# 01_MAIN.net
KiCad netlist of a schematic drawn in Altium Designer
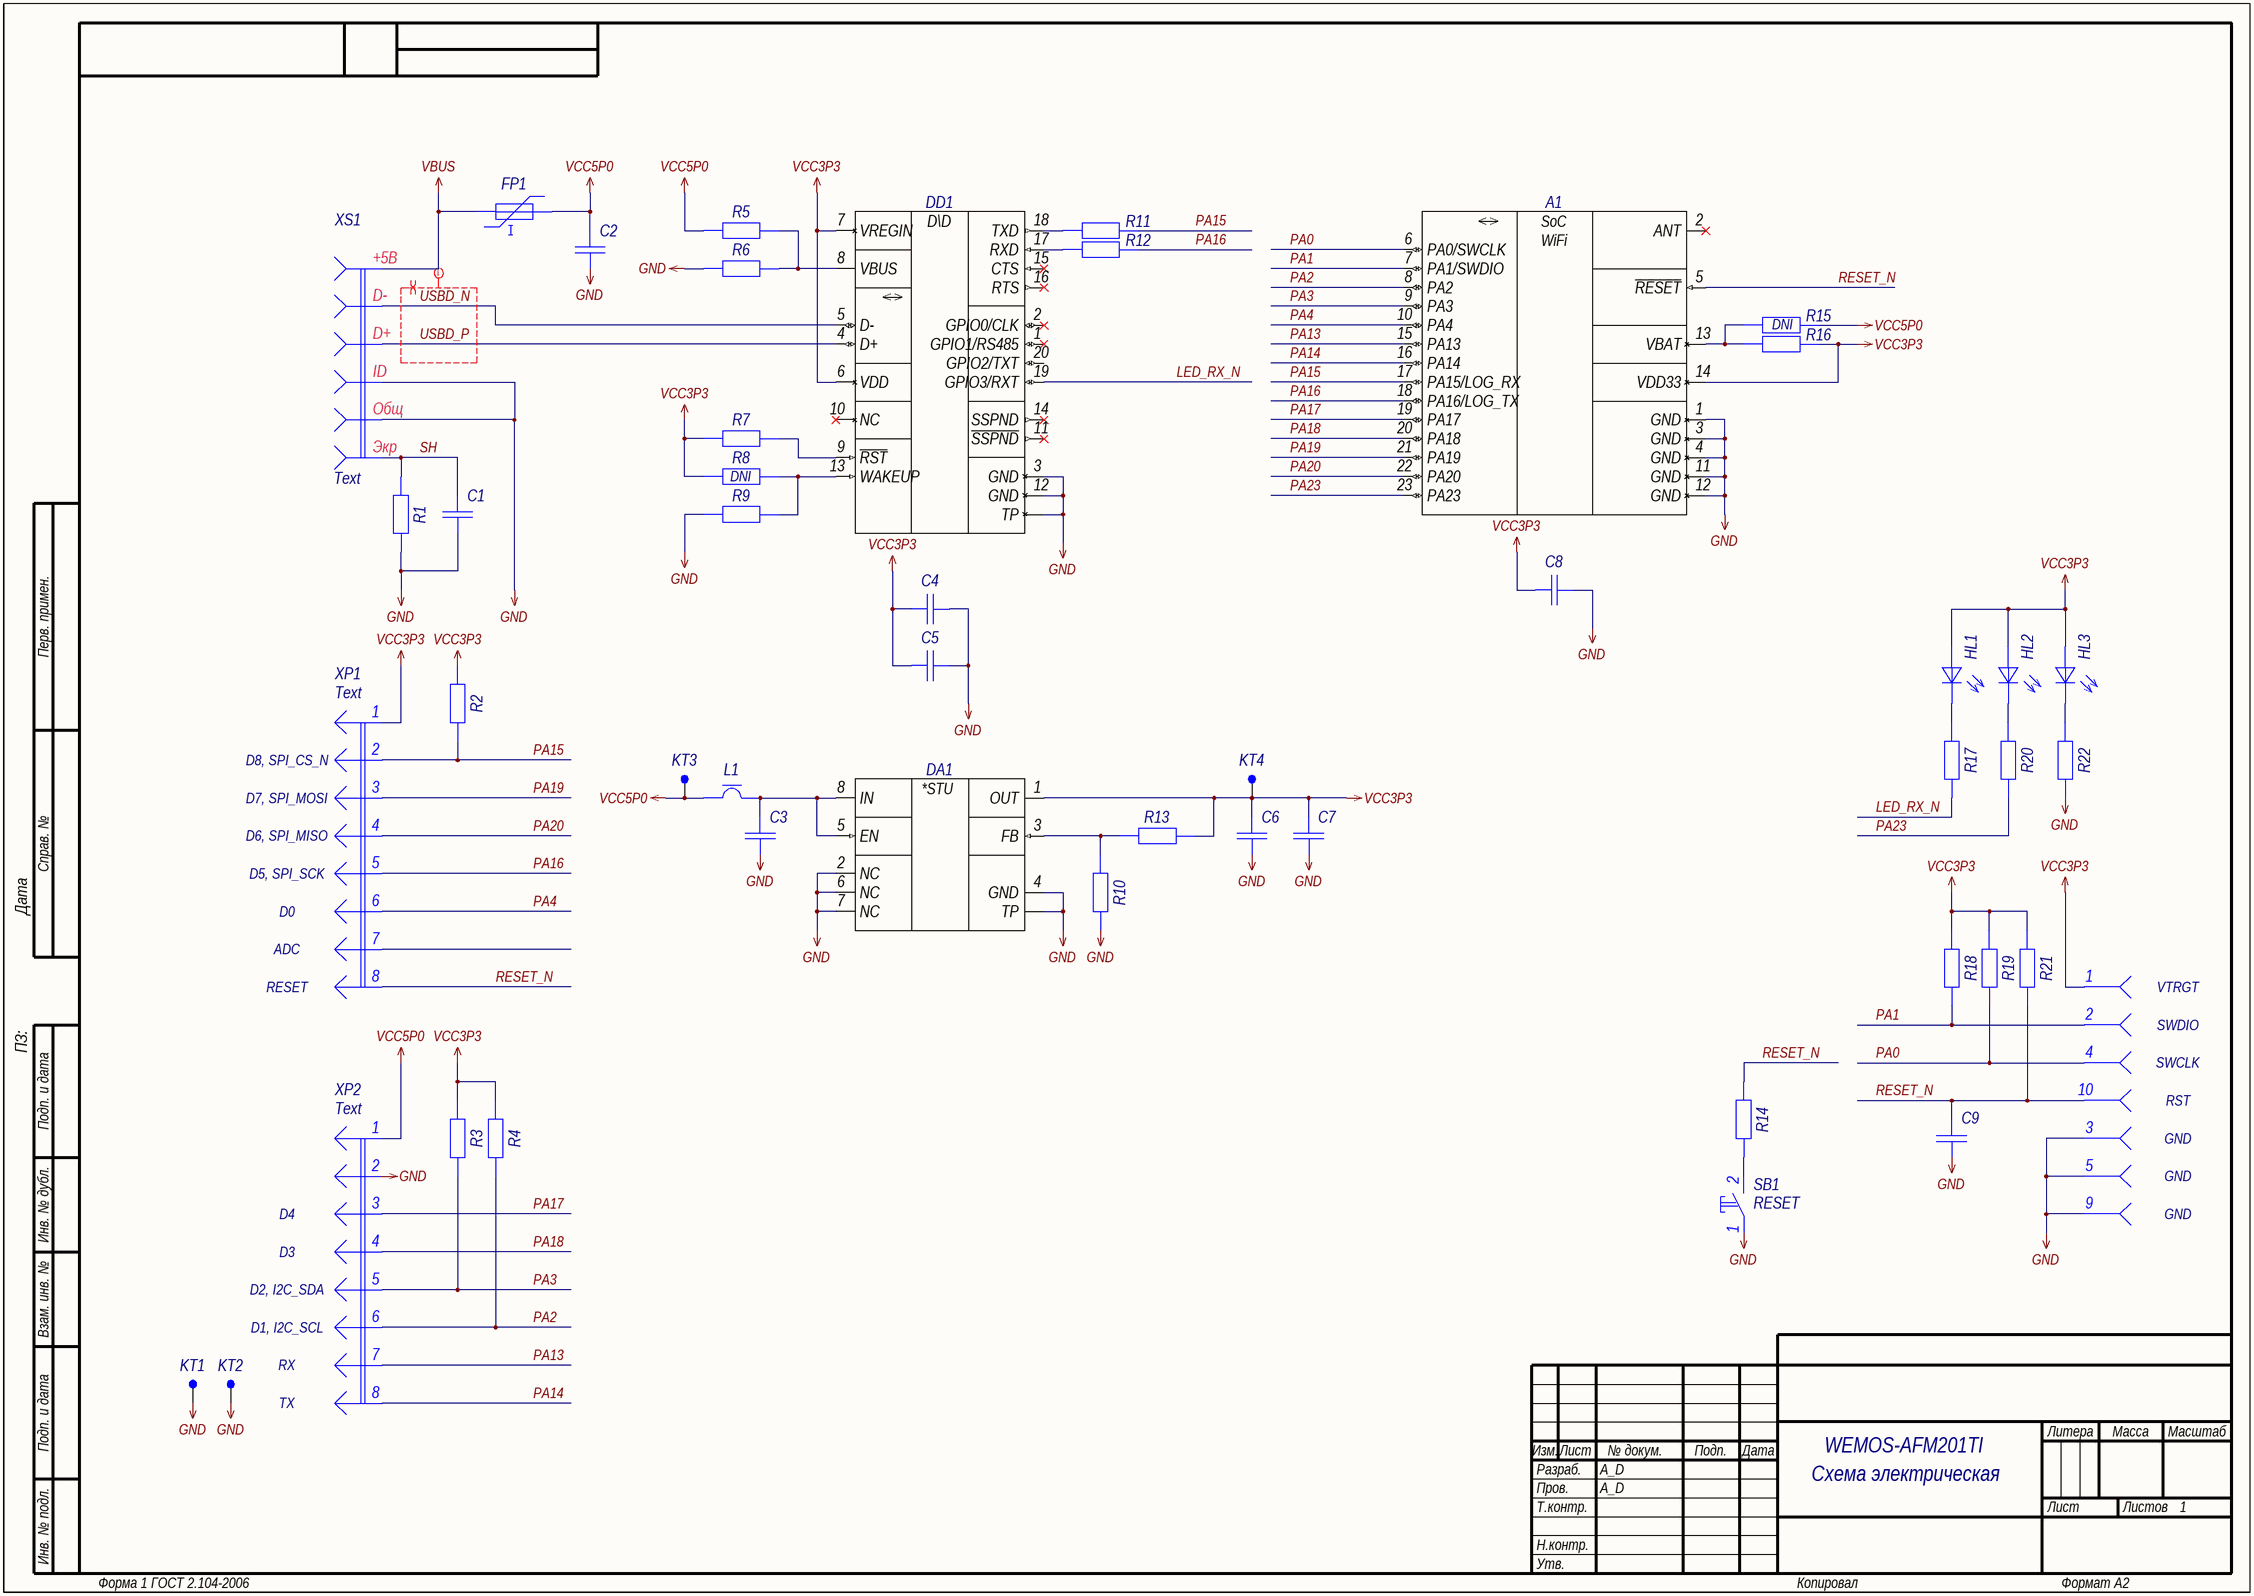
[diagram p0: 01_MAIN.SchDoc]

(export (version "E")
  (design (tool "Eeschema 10.0.6"))
  (components
    (comp (ref "A1")
      (value "AFM201Tx-Series")
      (footprint "AFM201Tx-Series")
      (fields
        (field (name "PART NUMBER") "AFM201TI")
        (field (name "MANUFACTURER") "99IOT")
        (field (name "PUBLISHER") "Andrew Danich")
      )
      (libsource (lib "ADLib") (part "AFM201Tx-Series"))
    )
    (comp (ref "C1")
      (value "Capacitor")
      (footprint "C0603_L")
      (fields
        (field (name "PART NUMBER") "GRM188R72A104KA35D")
        (field (name "VOLTAGE") "100V")
        (field (name "TOLERANCE") "±10%")
        (field (name "PUBLISHER") "Andrew Danich")
      )
      (libsource (lib "ADLib") (part "Capacitor"))
    )
    (comp (ref "C2")
      (value "Capacitor")
      (footprint "C0603_L")
      (fields
        (field (name "PART NUMBER") "GRM188R60J106ME47D")
        (field (name "VOLTAGE") "6.3V")
        (field (name "TOLERANCE") "±20%")
        (field (name "PUBLISHER") "Andrew Danich")
      )
      (libsource (lib "ADLib") (part "Capacitor"))
    )
    (comp (ref "C3")
      (value "Capacitor")
      (footprint "C0402_L")
      (fields
        (field (name "PART NUMBER") "GRM155R60J475ME87D")
        (field (name "VOLTAGE") "6.3V")
        (field (name "TOLERANCE") "±20%")
        (field (name "PUBLISHER") "Andrew Danich")
      )
      (libsource (lib "ADLib") (part "Capacitor"))
    )
    (comp (ref "C4")
      (value "Capacitor")
      (footprint "C0402_L")
      (fields
        (field (name "PART NUMBER") "GRM155R60J475ME87D")
        (field (name "VOLTAGE") "6.3V")
        (field (name "TOLERANCE") "±20%")
        (field (name "PUBLISHER") "Andrew Danich")
      )
      (libsource (lib "ADLib") (part "Capacitor"))
    )
    (comp (ref "C5")
      (value "Capacitor")
      (footprint "C0402_L")
      (fields
        (field (name "PART NUMBER") "GCM155R71C104KA55D")
        (field (name "VOLTAGE") "16V")
        (field (name "TOLERANCE") "±10%")
        (field (name "PUBLISHER") "Andrew Danich")
      )
      (libsource (lib "ADLib") (part "Capacitor"))
    )
    (comp (ref "C6")
      (value "Capacitor")
      (footprint "C0402_L")
      (fields
        (field (name "PART NUMBER") "GRM155R60J475ME87D")
        (field (name "VOLTAGE") "6.3V")
        (field (name "TOLERANCE") "±20%")
        (field (name "PUBLISHER") "Andrew Danich")
      )
      (libsource (lib "ADLib") (part "Capacitor"))
    )
    (comp (ref "C7")
      (value "Capacitor")
      (footprint "C0402_L")
      (fields
        (field (name "PART NUMBER") "GRM155R60J475ME87D")
        (field (name "VOLTAGE") "6.3V")
        (field (name "TOLERANCE") "±20%")
        (field (name "PUBLISHER") "Andrew Danich")
      )
      (libsource (lib "ADLib") (part "Capacitor"))
    )
    (comp (ref "C8")
      (value "Capacitor")
      (footprint "C0402_L")
      (fields
        (field (name "PART NUMBER") "GRM155R60J475ME87D")
        (field (name "VOLTAGE") "6.3V")
        (field (name "TOLERANCE") "±20%")
        (field (name "PUBLISHER") "Andrew Danich")
      )
      (libsource (lib "ADLib") (part "Capacitor"))
    )
    (comp (ref "C9")
      (value "Capacitor")
      (footprint "C0402_L")
      (fields
        (field (name "PART NUMBER") "GCM155R71C104KA55D")
        (field (name "VOLTAGE") "16V")
        (field (name "TOLERANCE") "±10%")
        (field (name "PUBLISHER") "Andrew Danich")
      )
      (libsource (lib "ADLib") (part "Capacitor"))
    )
    (comp (ref "DA1")
      (value "TPS73701DRB")
      (footprint "VSON-8_065P300X300X100_N")
      (fields
        (field (name "PART NUMBER") "TPS73701DRBR")
        (field (name "MANUFACTURER") "Texas Instruments")
        (field (name "PUBLISHER") "Andrew Danich")
      )
      (libsource (lib "ADLib") (part "TPS73701DRB"))
    )
    (comp (ref "DD1")
      (value "CP2102N-xxx-GQFN20")
      (footprint "QFN-20_050P300X300X080_N")
      (fields
        (field (name "PART NUMBER") "CP2102N-A01-GQFN20")
        (field (name "MANUFACTURER") "Silicon Labs")
        (field (name "PUBLISHER") "Andrew Danich")
      )
      (libsource (lib "ADLib") (part "CP2102N-xxx-GQFN20"))
    )
    (comp (ref "FP1")
      (value "Fuse_PTC")
      (footprint "F0603_L_H075")
      (fields (field (name "PART NUMBER") "0603L100SLYR") (field (name "MANUFACTURER") "Littelfuse"))
      (libsource (lib "ADLib") (part "Fuse_PTC"))
    )
    (comp (ref "HL1")
      (value "RX")
      (footprint "LD0402_L")
      (fields
        (field (name "PART NUMBER") "KPHHS-1005SURCK")
        (field (name "MANUFACTURER") "Kingbright")
        (field (name "PUBLISHER") "Andrew Danich")
      )
      (libsource (lib "ADLib") (part "Led-1"))
    )
    (comp (ref "HL2")
      (value "USER")
      (footprint "LD0402_L")
      (fields
        (field (name "PART NUMBER") "KPHHS-1005QBC-D-V")
        (field (name "MANUFACTURER") "Kingbright")
        (field (name "PUBLISHER") "Andrew Danich")
      )
      (libsource (lib "ADLib") (part "Led-1"))
    )
    (comp (ref "HL3")
      (value "POWER")
      (footprint "LD0402_L")
      (fields
        (field (name "PART NUMBER") "KPHHS-1005CGCK")
        (field (name "MANUFACTURER") "Kingbright")
        (field (name "PUBLISHER") "Andrew Danich")
      )
      (libsource (lib "ADLib") (part "Led-1"))
    )
    (comp (ref "KT1")
      (value "GND")
      (footprint "TP-SMT-R-0.8mm")
      (fields (field (name "PART NUMBER") "TestPoint-SMT-GND") (field (name "PUBLISHER") "Andrew Danich"))
      (libsource (lib "ADLib") (part "TP-S-1"))
    )
    (comp (ref "KT2")
      (value "GND")
      (footprint "TP-SMT-R-0.8mm")
      (fields (field (name "PART NUMBER") "TestPoint-SMT-GND") (field (name "PUBLISHER") "Andrew Danich"))
      (libsource (lib "ADLib") (part "TP-S-1"))
    )
    (comp (ref "KT3")
      (value "5P0")
      (footprint "TP-SMT-C-0.5mm")
      (fields (field (name "PART NUMBER") "TestPoint-SMT") (field (name "PUBLISHER") "Andrew Danich"))
      (libsource (lib "ADLib") (part "TP-S-1"))
    )
    (comp (ref "KT4")
      (value "3P3")
      (footprint "TP-SMT-C-0.5mm")
      (fields (field (name "PART NUMBER") "TestPoint-SMT") (field (name "PUBLISHER") "Andrew Danich"))
      (libsource (lib "ADLib") (part "TP-S-1"))
    )
    (comp (ref "L1")
      (value "FerriteBead")
      (footprint "L0402_L")
      (fields
        (field (name "PART NUMBER") "BLM15PD121SN1D")
        (field (name "TOLERANCE") "±25%")
        (field (name "MANUFACTURER") "Murata")
        (field (name "PUBLISHER") "Andrew Danich")
      )
      (libsource (lib "ADLib") (part "FerriteBead"))
    )
    (comp (ref "R1")
      (value "Resistor")
      (footprint "R0603_L")
      (fields
        (field (name "PART NUMBER") "RC0603JR-070R")
        (field (name "TOLERANCE") "±5%")
        (field (name "MANUFACTURER") "Yageo")
        (field (name "PUBLISHER") "Andrew Danich")
      )
      (libsource (lib "ADLib") (part "Resistor"))
    )
    (comp (ref "R2")
      (value "Resistor")
      (footprint "R0402_L")
      (fields
        (field (name "PART NUMBER") "RC0402JR-0710KL")
        (field (name "TOLERANCE") "±5%")
        (field (name "MANUFACTURER") "Yageo")
        (field (name "PUBLISHER") "Andrew Danich")
      )
      (libsource (lib "ADLib") (part "Resistor"))
    )
    (comp (ref "R3")
      (value "Resistor")
      (footprint "R0402_L")
      (fields
        (field (name "PART NUMBER") "RC0402JR-0710KL")
        (field (name "TOLERANCE") "±5%")
        (field (name "MANUFACTURER") "Yageo")
        (field (name "PUBLISHER") "Andrew Danich")
      )
      (libsource (lib "ADLib") (part "Resistor"))
    )
    (comp (ref "R4")
      (value "Resistor")
      (footprint "R0402_L")
      (fields
        (field (name "PART NUMBER") "RC0402JR-0710KL")
        (field (name "TOLERANCE") "±5%")
        (field (name "MANUFACTURER") "Yageo")
        (field (name "PUBLISHER") "Andrew Danich")
      )
      (libsource (lib "ADLib") (part "Resistor"))
    )
    (comp (ref "R5")
      (value "Resistor")
      (footprint "R0402_L")
      (fields
        (field (name "PART NUMBER") "RC0402FR-0722K1L")
        (field (name "TOLERANCE") "±1%")
        (field (name "MANUFACTURER") "Yageo")
        (field (name "PUBLISHER") "Andrew Danich")
      )
      (libsource (lib "ADLib") (part "Resistor"))
    )
    (comp (ref "R6")
      (value "Resistor")
      (footprint "R0402_L")
      (fields
        (field (name "PART NUMBER") "RC0402FR-0747KL")
        (field (name "TOLERANCE") "±1%")
        (field (name "MANUFACTURER") "Yageo")
        (field (name "PUBLISHER") "Andrew Danich")
      )
      (libsource (lib "ADLib") (part "Resistor"))
    )
    (comp (ref "R7")
      (value "Resistor")
      (footprint "R0402_L")
      (fields
        (field (name "PART NUMBER") "RC0402JR-0710KL")
        (field (name "TOLERANCE") "±5%")
        (field (name "MANUFACTURER") "Yageo")
        (field (name "PUBLISHER") "Andrew Danich")
      )
      (libsource (lib "ADLib") (part "Resistor"))
    )
    (comp (ref "R8")
      (value "Resistor")
      (footprint "R0402_L")
      (fields
        (field (name "PART NUMBER") "RC0402JR-0710KL")
        (field (name "TOLERANCE") "±5%")
        (field (name "MANUFACTURER") "Yageo")
        (field (name "PUBLISHER") "Andrew Danich")
      )
      (libsource (lib "ADLib") (part "Resistor"))
    )
    (comp (ref "R9")
      (value "Resistor")
      (footprint "R0402_L")
      (fields
        (field (name "PART NUMBER") "RC0402JR-070RL")
        (field (name "TOLERANCE") "±5%")
        (field (name "MANUFACTURER") "Yageo")
        (field (name "PUBLISHER") "Andrew Danich")
      )
      (libsource (lib "ADLib") (part "Resistor"))
    )
    (comp (ref "R10")
      (value "Resistor")
      (footprint "R0402_L")
      (fields
        (field (name "PART NUMBER") "RC0402FR-0712KL")
        (field (name "TOLERANCE") "±1%")
        (field (name "MANUFACTURER") "Yageo")
        (field (name "PUBLISHER") "Andrew Danich")
      )
      (libsource (lib "ADLib") (part "Resistor"))
    )
    (comp (ref "R11")
      (value "Resistor")
      (footprint "R0402_L")
      (fields
        (field (name "PART NUMBER") "RC0402JR-070RL")
        (field (name "TOLERANCE") "±5%")
        (field (name "MANUFACTURER") "Yageo")
        (field (name "PUBLISHER") "Andrew Danich")
      )
      (libsource (lib "ADLib") (part "Resistor"))
    )
    (comp (ref "R12")
      (value "Resistor")
      (footprint "R0402_L")
      (fields
        (field (name "PART NUMBER") "RC0402JR-070RL")
        (field (name "TOLERANCE") "±5%")
        (field (name "MANUFACTURER") "Yageo")
        (field (name "PUBLISHER") "Andrew Danich")
      )
      (libsource (lib "ADLib") (part "Resistor"))
    )
    (comp (ref "R13")
      (value "Resistor")
      (footprint "R0402_L")
      (fields
        (field (name "PART NUMBER") "RC0402FR-0722K1L")
        (field (name "TOLERANCE") "±1%")
        (field (name "MANUFACTURER") "Yageo")
        (field (name "PUBLISHER") "Andrew Danich")
      )
      (libsource (lib "ADLib") (part "Resistor"))
    )
    (comp (ref "R14")
      (value "Resistor")
      (footprint "R0402_L")
      (fields
        (field (name "PART NUMBER") "RC0402JR-0720RL")
        (field (name "TOLERANCE") "±5%")
        (field (name "MANUFACTURER") "Yageo")
        (field (name "PUBLISHER") "Andrew Danich")
      )
      (libsource (lib "ADLib") (part "Resistor"))
    )
    (comp (ref "R15")
      (value "Resistor")
      (footprint "R0402_L")
      (fields
        (field (name "PART NUMBER") "RC0402JR-070RL")
        (field (name "TOLERANCE") "±5%")
        (field (name "MANUFACTURER") "Yageo")
        (field (name "PUBLISHER") "Andrew Danich")
      )
      (libsource (lib "ADLib") (part "Resistor"))
    )
    (comp (ref "R16")
      (value "Resistor")
      (footprint "R0402_L")
      (fields
        (field (name "PART NUMBER") "RC0402JR-070RL")
        (field (name "TOLERANCE") "±5%")
        (field (name "MANUFACTURER") "Yageo")
        (field (name "PUBLISHER") "Andrew Danich")
      )
      (libsource (lib "ADLib") (part "Resistor"))
    )
    (comp (ref "R17")
      (value "Resistor")
      (footprint "R0402_L")
      (fields
        (field (name "PART NUMBER") "RC0402JR-071KL")
        (field (name "TOLERANCE") "±5%")
        (field (name "MANUFACTURER") "Yageo")
        (field (name "PUBLISHER") "Andrew Danich")
      )
      (libsource (lib "ADLib") (part "Resistor"))
    )
    (comp (ref "R18")
      (value "Resistor")
      (footprint "R0402_L")
      (fields
        (field (name "PART NUMBER") "RC0402JR-0710KL")
        (field (name "TOLERANCE") "±5%")
        (field (name "MANUFACTURER") "Yageo")
        (field (name "PUBLISHER") "Andrew Danich")
      )
      (libsource (lib "ADLib") (part "Resistor"))
    )
    (comp (ref "R19")
      (value "Resistor")
      (footprint "R0402_L")
      (fields
        (field (name "PART NUMBER") "RC0402JR-0710KL")
        (field (name "TOLERANCE") "±5%")
        (field (name "MANUFACTURER") "Yageo")
        (field (name "PUBLISHER") "Andrew Danich")
      )
      (libsource (lib "ADLib") (part "Resistor"))
    )
    (comp (ref "R20")
      (value "Resistor")
      (footprint "R0402_L")
      (fields
        (field (name "PART NUMBER") "RC0402JR-071KL")
        (field (name "TOLERANCE") "±5%")
        (field (name "MANUFACTURER") "Yageo")
        (field (name "PUBLISHER") "Andrew Danich")
      )
      (libsource (lib "ADLib") (part "Resistor"))
    )
    (comp (ref "R21")
      (value "Resistor")
      (footprint "R0402_L")
      (fields
        (field (name "PART NUMBER") "RC0402JR-0710KL")
        (field (name "TOLERANCE") "±5%")
        (field (name "MANUFACTURER") "Yageo")
        (field (name "PUBLISHER") "Andrew Danich")
      )
      (libsource (lib "ADLib") (part "Resistor"))
    )
    (comp (ref "R22")
      (value "Resistor")
      (footprint "R0402_L")
      (fields
        (field (name "PART NUMBER") "RC0402JR-071KL")
        (field (name "TOLERANCE") "±5%")
        (field (name "MANUFACTURER") "Yageo")
        (field (name "PUBLISHER") "Andrew Danich")
      )
      (libsource (lib "ADLib") (part "Resistor"))
    )
    (comp (ref "SB1")
      (value "RESET")
      (footprint "1TS003B-Series")
      (fields
        (field (name "PART NUMBER") "1TS003B-1600-3500A-CT")
        (field (name "MANUFACTURER") "Hongyuan Precision")
        (field (name "PUBLISHER") "Andrew Danich")
      )
      (libsource (lib "ADLib") (part "BT-01x-01p"))
    )
    (comp (ref "XP1")
      (value "Text")
      (footprint "PLS-8")
      (fields (field (name "PART NUMBER") "PLS-8") (field (name "PUBLISHER") "Andrew Danich"))
      (libsource (lib "ADLib") (part "Con-8-M"))
    )
    (comp (ref "XP2")
      (value "Text")
      (footprint "PLS-8")
      (fields (field (name "PART NUMBER") "PLS-8") (field (name "PUBLISHER") "Andrew Danich"))
      (libsource (lib "ADLib") (part "Con-8-M"))
    )
    (comp (ref "XS1")
      (value "Text")
      (footprint "1981568-1")
      (fields
        (field (name "PART NUMBER") "1981568-1")
        (field (name "MANUFACTURER") "TE Connectivity")
        (field (name "PUBLISHER") "Andrew Danich")
      )
      (libsource (lib "ADLib") (part "Con-6-F-USB"))
    )
    (comp (ref "XS2")
      (value "JTAG")
      (footprint "XF2M-1015-1A")
      (fields
        (field (name "PART NUMBER") "XF2M-1015-1A")
        (field (name "MANUFACTURER") "Omron Electronics")
        (field (name "PUBLISHER") "Viktor Klishin")
      )
      (libsource (lib "ADLib") (part "Con-10-F_S"))
    )
  )
  (nets
    (net (code "1") (name "/LED_RX_N") (class "Default")
      (node (ref "DD1") (pin "19") (pinfunction "GPIO3/RXT_19") (pintype "bidirectional"))
      (node (ref "R17") (pin "1") (pinfunction "1_1") (pintype "passive"))
    )
    (net (code "2") (name "/PA0") (class "Default")
      (node (ref "A1") (pin "6") (pinfunction "PA0/SWCLK_6") (pintype "bidirectional"))
      (node (ref "R19") (pin "2") (pinfunction "2_2") (pintype "passive"))
      (node (ref "XS2") (pin "4") (pintype "passive"))
    )
    (net (code "3") (name "/PA1") (class "Default")
      (node (ref "A1") (pin "7") (pinfunction "PA1/SWDIO_7") (pintype "bidirectional"))
      (node (ref "R18") (pin "2") (pinfunction "2_2") (pintype "passive"))
      (node (ref "XS2") (pin "2") (pintype "passive"))
    )
    (net (code "4") (name "/PA2") (class "Default")
      (node (ref "A1") (pin "8") (pinfunction "PA2_8") (pintype "bidirectional"))
      (node (ref "R4") (pin "2") (pinfunction "2_2") (pintype "passive"))
      (node (ref "XP2") (pin "6") (pintype "passive"))
    )
    (net (code "5") (name "/PA3") (class "Default")
      (node (ref "A1") (pin "9") (pinfunction "PA3_9") (pintype "bidirectional"))
      (node (ref "R3") (pin "2") (pinfunction "2_2") (pintype "passive"))
      (node (ref "XP2") (pin "5") (pintype "passive"))
    )
    (net (code "6") (name "/PA4") (class "Default")
      (node (ref "A1") (pin "10") (pinfunction "PA4_10") (pintype "bidirectional"))
      (node (ref "XP1") (pin "6") (pintype "passive"))
    )
    (net (code "7") (name "/PA13") (class "Default")
      (node (ref "A1") (pin "15") (pinfunction "PA13_15") (pintype "bidirectional"))
      (node (ref "XP2") (pin "7") (pintype "passive"))
    )
    (net (code "8") (name "/PA14") (class "Default")
      (node (ref "A1") (pin "16") (pinfunction "PA14_16") (pintype "bidirectional"))
      (node (ref "XP2") (pin "8") (pintype "passive"))
    )
    (net (code "9") (name "/PA15") (class "Default")
      (node (ref "A1") (pin "17") (pinfunction "PA15/LOG_RX_17") (pintype "bidirectional"))
      (node (ref "R11") (pin "2") (pinfunction "2_2") (pintype "passive"))
      (node (ref "R2") (pin "2") (pinfunction "2_2") (pintype "passive"))
      (node (ref "XP1") (pin "2") (pintype "passive"))
    )
    (net (code "10") (name "/PA16") (class "Default")
      (node (ref "A1") (pin "18") (pinfunction "PA16/LOG_TX_18") (pintype "bidirectional"))
      (node (ref "R12") (pin "2") (pinfunction "2_2") (pintype "passive"))
      (node (ref "XP1") (pin "5") (pintype "passive"))
    )
    (net (code "11") (name "/PA17") (class "Default")
      (node (ref "A1") (pin "19") (pinfunction "PA17_19") (pintype "bidirectional"))
      (node (ref "XP2") (pin "3") (pintype "passive"))
    )
    (net (code "12") (name "/PA18") (class "Default")
      (node (ref "A1") (pin "20") (pinfunction "PA18_20") (pintype "bidirectional"))
      (node (ref "XP2") (pin "4") (pintype "passive"))
    )
    (net (code "13") (name "/PA19") (class "Default")
      (node (ref "A1") (pin "21") (pinfunction "PA19_21") (pintype "bidirectional"))
      (node (ref "XP1") (pin "3") (pintype "passive"))
    )
    (net (code "14") (name "/PA20") (class "Default")
      (node (ref "A1") (pin "22") (pinfunction "PA20_22") (pintype "bidirectional"))
      (node (ref "XP1") (pin "4") (pintype "passive"))
    )
    (net (code "15") (name "/PA23") (class "Default")
      (node (ref "A1") (pin "23") (pinfunction "PA23_23") (pintype "bidirectional"))
      (node (ref "R20") (pin "1") (pinfunction "1_1") (pintype "passive"))
    )
    (net (code "16") (name "/RESET_N") (class "Default")
      (node (ref "A1") (pin "5") (pinfunction "~{RESET}_5") (pintype "input"))
      (node (ref "C9") (pin "2") (pinfunction "2_2") (pintype "passive"))
      (node (ref "R14") (pin "2") (pinfunction "2_2") (pintype "passive"))
      (node (ref "R21") (pin "2") (pinfunction "2_2") (pintype "passive"))
      (node (ref "XP1") (pin "8") (pintype "passive"))
      (node (ref "XS2") (pin "10") (pintype "passive"))
    )
    (net (code "17") (name "/SH") (class "Default")
      (node (ref "C1") (pin "2") (pinfunction "2_2") (pintype "passive"))
      (node (ref "R1") (pin "2") (pinfunction "2_2") (pintype "passive"))
      (node (ref "XS1") (pin "6") (pintype "passive"))
    )
    (net (code "18") (name "/USBD_N") (class "Default")
      (node (ref "DD1") (pin "5") (pinfunction "D-_5") (pintype "bidirectional"))
      (node (ref "XS1") (pin "2") (pintype "passive"))
    )
    (net (code "19") (name "/USBD_P") (class "Default")
      (node (ref "DD1") (pin "4") (pinfunction "D+_4") (pintype "bidirectional"))
      (node (ref "XS1") (pin "3") (pintype "passive"))
    )
    (net (code "20") (name "GND") (class "Default")
      (node (ref "A1") (pin "1") (pinfunction "GND_1") (pintype "power_in"))
      (node (ref "A1") (pin "11") (pinfunction "GND_11") (pintype "power_in"))
      (node (ref "A1") (pin "12") (pinfunction "GND_12") (pintype "power_in"))
      (node (ref "A1") (pin "3") (pinfunction "GND_3") (pintype "power_in"))
      (node (ref "A1") (pin "4") (pinfunction "GND_4") (pintype "power_in"))
      (node (ref "C1") (pin "1") (pinfunction "1_1") (pintype "passive"))
      (node (ref "C2") (pin "1") (pinfunction "1_1") (pintype "passive"))
      (node (ref "C3") (pin "1") (pinfunction "1_1") (pintype "passive"))
      (node (ref "C4") (pin "1") (pinfunction "1_1") (pintype "passive"))
      (node (ref "C5") (pin "1") (pinfunction "1_1") (pintype "passive"))
      (node (ref "C6") (pin "1") (pinfunction "1_1") (pintype "passive"))
      (node (ref "C7") (pin "1") (pinfunction "1_1") (pintype "passive"))
      (node (ref "C8") (pin "1") (pinfunction "1_1") (pintype "passive"))
      (node (ref "C9") (pin "1") (pinfunction "1_1") (pintype "passive"))
      (node (ref "DA1") (pin "2") (pinfunction "NC_2") (pintype "passive"))
      (node (ref "DA1") (pin "4") (pinfunction "GND_4") (pintype "power_in"))
      (node (ref "DA1") (pin "6") (pinfunction "NC_6") (pintype "passive"))
      (node (ref "DA1") (pin "7") (pinfunction "NC_7") (pintype "passive"))
      (node (ref "DA1") (pin "TP") (pinfunction "TP_TP") (pintype "passive"))
      (node (ref "DD1") (pin "12") (pinfunction "GND_12") (pintype "power_in"))
      (node (ref "DD1") (pin "3") (pinfunction "GND_3") (pintype "power_in"))
      (node (ref "DD1") (pin "TP") (pinfunction "TP_TP") (pintype "power_in"))
      (node (ref "KT1") (pin "1") (pinfunction "1_1") (pintype "passive"))
      (node (ref "KT2") (pin "1") (pinfunction "1_1") (pintype "passive"))
      (node (ref "R1") (pin "1") (pinfunction "1_1") (pintype "passive"))
      (node (ref "R10") (pin "1") (pinfunction "1_1") (pintype "passive"))
      (node (ref "R22") (pin "1") (pinfunction "1_1") (pintype "passive"))
      (node (ref "R6") (pin "1") (pinfunction "1_1") (pintype "passive"))
      (node (ref "R9") (pin "1") (pinfunction "1_1") (pintype "passive"))
      (node (ref "SB1") (pin "1") (pintype "passive"))
      (node (ref "XP2") (pin "2") (pintype "passive"))
      (node (ref "XS1") (pin "4") (pintype "passive"))
      (node (ref "XS1") (pin "5") (pintype "passive"))
      (node (ref "XS2") (pin "3") (pintype "passive"))
      (node (ref "XS2") (pin "5") (pintype "passive"))
      (node (ref "XS2") (pin "9") (pintype "passive"))
    )
    (net (code "21") (name "Net-(A1-VBAT)") (class "Default")
      (node (ref "A1") (pin "13") (pinfunction "VBAT_13") (pintype "power_in"))
      (node (ref "R15") (pin "1") (pinfunction "1_1") (pintype "passive"))
      (node (ref "R16") (pin "1") (pinfunction "1_1") (pintype "passive"))
    )
    (net (code "22") (name "Net-(DA1-EN)") (class "Default")
      (node (ref "C3") (pin "2") (pinfunction "2_2") (pintype "passive"))
      (node (ref "DA1") (pin "5") (pinfunction "EN_5") (pintype "input"))
      (node (ref "DA1") (pin "8") (pinfunction "IN_8") (pintype "power_in"))
      (node (ref "L1") (pin "2") (pinfunction "2_2") (pintype "passive"))
    )
    (net (code "23") (name "Net-(DA1-FB)") (class "Default")
      (node (ref "DA1") (pin "3") (pinfunction "FB_3") (pintype "input"))
      (node (ref "R10") (pin "2") (pinfunction "2_2") (pintype "passive"))
      (node (ref "R13") (pin "1") (pinfunction "1_1") (pintype "passive"))
    )
    (net (code "24") (name "Net-(DD1-RXD)") (class "Default")
      (node (ref "DD1") (pin "17") (pinfunction "RXD_17") (pintype "input"))
      (node (ref "R12") (pin "1") (pinfunction "1_1") (pintype "passive"))
    )
    (net (code "25") (name "Net-(DD1-TXD)") (class "Default")
      (node (ref "DD1") (pin "18") (pinfunction "TXD_18") (pintype "output"))
      (node (ref "R11") (pin "1") (pinfunction "1_1") (pintype "passive"))
    )
    (net (code "26") (name "Net-(DD1-VBUS)") (class "Default")
      (node (ref "DD1") (pin "8") (pinfunction "VBUS_8") (pintype "power_in"))
      (node (ref "R5") (pin "2") (pinfunction "2_2") (pintype "passive"))
      (node (ref "R6") (pin "2") (pinfunction "2_2") (pintype "passive"))
    )
    (net (code "27") (name "Net-(DD1-WAKEUP)") (class "Default")
      (node (ref "DD1") (pin "13") (pinfunction "WAKEUP_13") (pintype "input"))
      (node (ref "R8") (pin "1") (pinfunction "1_1") (pintype "passive"))
      (node (ref "R9") (pin "2") (pinfunction "2_2") (pintype "passive"))
    )
    (net (code "28") (name "Net-(DD1-~{RST})") (class "Default")
      (node (ref "DD1") (pin "9") (pinfunction "~{RST}_9") (pintype "input"))
      (node (ref "R7") (pin "1") (pinfunction "1_1") (pintype "passive"))
    )
    (net (code "29") (name "Net-(HL1-К)") (class "Default")
      (node (ref "HL1") (pin "2") (pinfunction "К_2") (pintype "passive"))
      (node (ref "R17") (pin "2") (pinfunction "2_2") (pintype "passive"))
    )
    (net (code "30") (name "Net-(HL2-К)") (class "Default")
      (node (ref "HL2") (pin "2") (pinfunction "К_2") (pintype "passive"))
      (node (ref "R20") (pin "2") (pinfunction "2_2") (pintype "passive"))
    )
    (net (code "31") (name "Net-(HL3-К)") (class "Default")
      (node (ref "HL3") (pin "2") (pinfunction "К_2") (pintype "passive"))
      (node (ref "R22") (pin "2") (pinfunction "2_2") (pintype "passive"))
    )
    (net (code "32") (name "Net-(R14-Pad1)") (class "Default")
      (node (ref "R14") (pin "1") (pinfunction "1_1") (pintype "passive"))
      (node (ref "SB1") (pin "2") (pintype "passive"))
    )
    (net (code "33") (name "VBUS") (class "Default")
      (node (ref "FP1") (pin "1") (pinfunction "1_1") (pintype "passive"))
      (node (ref "XS1") (pin "1") (pintype "passive"))
    )
    (net (code "34") (name "VCC3P3") (class "Default")
      (node (ref "A1") (pin "14") (pinfunction "VDD33_14") (pintype "power_in"))
      (node (ref "C4") (pin "2") (pinfunction "2_2") (pintype "passive"))
      (node (ref "C5") (pin "2") (pinfunction "2_2") (pintype "passive"))
      (node (ref "C6") (pin "2") (pinfunction "2_2") (pintype "passive"))
      (node (ref "C7") (pin "2") (pinfunction "2_2") (pintype "passive"))
      (node (ref "C8") (pin "2") (pinfunction "2_2") (pintype "passive"))
      (node (ref "DA1") (pin "1") (pinfunction "OUT_1") (pintype "power_in"))
      (node (ref "DD1") (pin "6") (pinfunction "VDD_6") (pintype "power_in"))
      (node (ref "DD1") (pin "7") (pinfunction "VREGIN_7") (pintype "power_in"))
      (node (ref "HL1") (pin "1") (pinfunction "А_1") (pintype "passive"))
      (node (ref "HL2") (pin "1") (pinfunction "А_1") (pintype "passive"))
      (node (ref "HL3") (pin "1") (pinfunction "А_1") (pintype "passive"))
      (node (ref "KT4") (pin "1") (pinfunction "1_1") (pintype "passive"))
      (node (ref "R13") (pin "2") (pinfunction "2_2") (pintype "passive"))
      (node (ref "R16") (pin "2") (pinfunction "2_2") (pintype "passive"))
      (node (ref "R18") (pin "1") (pinfunction "1_1") (pintype "passive"))
      (node (ref "R19") (pin "1") (pinfunction "1_1") (pintype "passive"))
      (node (ref "R2") (pin "1") (pinfunction "1_1") (pintype "passive"))
      (node (ref "R21") (pin "1") (pinfunction "1_1") (pintype "passive"))
      (node (ref "R3") (pin "1") (pinfunction "1_1") (pintype "passive"))
      (node (ref "R4") (pin "1") (pinfunction "1_1") (pintype "passive"))
      (node (ref "R7") (pin "2") (pinfunction "2_2") (pintype "passive"))
      (node (ref "R8") (pin "2") (pinfunction "2_2") (pintype "passive"))
      (node (ref "XP1") (pin "1") (pintype "passive"))
      (node (ref "XS2") (pin "1") (pintype "passive"))
    )
    (net (code "35") (name "VCC5P0") (class "Default")
      (node (ref "C2") (pin "2") (pinfunction "2_2") (pintype "passive"))
      (node (ref "FP1") (pin "2") (pinfunction "2_2") (pintype "passive"))
      (node (ref "KT3") (pin "1") (pinfunction "1_1") (pintype "passive"))
      (node (ref "L1") (pin "1") (pinfunction "1_1") (pintype "passive"))
      (node (ref "R15") (pin "2") (pinfunction "2_2") (pintype "passive"))
      (node (ref "R5") (pin "1") (pinfunction "1_1") (pintype "passive"))
      (node (ref "XP2") (pin "1") (pintype "passive"))
    )
    (net (code "36") (name "unconnected-(A1-ANT-Pad2)") (class "Default")
      (node (ref "A1") (pin "2") (pinfunction "ANT_2") (pintype "passive+no_connect"))
    )
    (net (code "37") (name "unconnected-(DD1-CTS-Pad15)") (class "Default")
      (node (ref "DD1") (pin "15") (pinfunction "CTS_15") (pintype "input+no_connect"))
    )
    (net (code "38") (name "unconnected-(DD1-GPIO0{slash}CLK-Pad2)") (class "Default")
      (node (ref "DD1") (pin "2") (pinfunction "GPIO0/CLK_2") (pintype "bidirectional+no_connect"))
    )
    (net (code "39") (name "unconnected-(DD1-GPIO1{slash}RS485-Pad1)") (class "Default")
      (node (ref "DD1") (pin "1") (pinfunction "GPIO1/RS485_1") (pintype "bidirectional+no_connect"))
    )
    (net (code "40") (name "unconnected-(DD1-GPIO2{slash}TXT-Pad20)") (class "Default")
      (node (ref "DD1") (pin "20") (pinfunction "GPIO2/TXT_20") (pintype "bidirectional"))
    )
    (net (code "41") (name "unconnected-(DD1-NC-Pad10)") (class "Default")
      (node (ref "DD1") (pin "10") (pinfunction "NC_10") (pintype "passive+no_connect"))
    )
    (net (code "42") (name "unconnected-(DD1-RTS-Pad16)") (class "Default")
      (node (ref "DD1") (pin "16") (pinfunction "RTS_16") (pintype "output+no_connect"))
    )
    (net (code "43") (name "unconnected-(DD1-SSPND-Pad14)") (class "Default")
      (node (ref "DD1") (pin "14") (pinfunction "SSPND_14") (pintype "output+no_connect"))
    )
    (net (code "44") (name "unconnected-(DD1-~{SSPND}-Pad11)") (class "Default")
      (node (ref "DD1") (pin "11") (pinfunction "~{SSPND}_11") (pintype "output+no_connect"))
    )
    (net (code "45") (name "unconnected-(XP1-Pad7)") (class "Default")
      (node (ref "XP1") (pin "7") (pintype "passive"))
    )
  )
)
